# shield.net
KiCad netlist of a schematic drawn in EAGLE
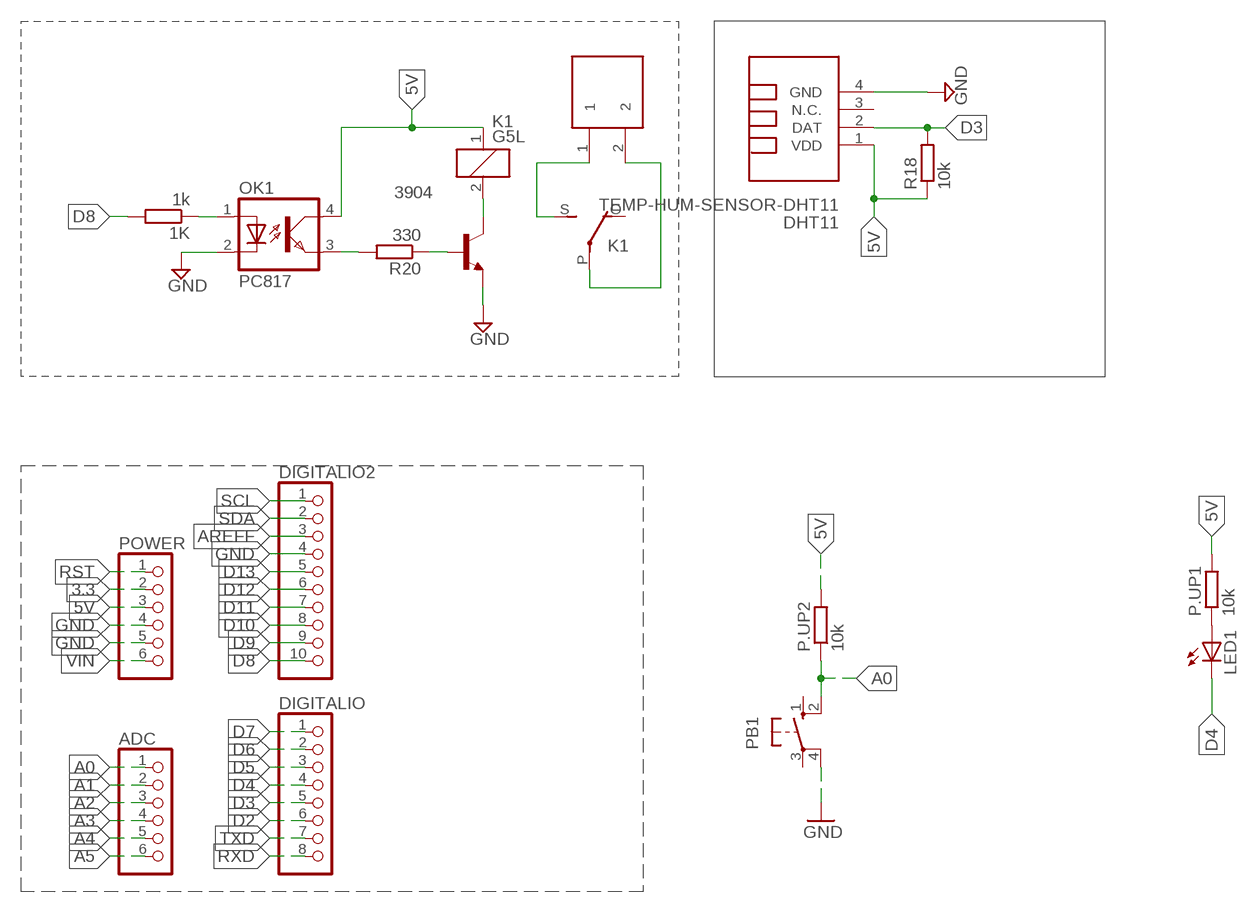
[diagram p0: schematic, sheet 1]

(export (version "E")
  (design (tool "Eeschema 10.0.6"))
  (components
    (comp (ref "1K")
      (value "1k")
      (footprint "eagle-import:R0805")
      (libsource (lib "eagle-import") (part "R-EU_R0805"))
    )
    (comp (ref "3904")
      (value "MMBT3904LT1-NPN-SOT23-BEC")
      (footprint "eagle-import:SOT23-BEC")
      (libsource (lib "eagle-import") (part "-NPN-SOT23-BECMMBT3904LT1"))
    )
    (comp (ref "ADC")
      (value "PINHD-1X6")
      (footprint "eagle-import:1X06")
      (libsource (lib "eagle-import") (part "PINHD-1X6"))
    )
    (comp (ref "DHT11")
      (value "TEMP-HUM-SENSOR-DHT11")
      (footprint "eagle-import:TEMP-HUM-SENSOR-DHT11")
      (libsource (lib "eagle-import") (part "TEMP-HUM-SENSOR-DHT11"))
    )
    (comp (ref "DIGITALIO")
      (value "PINHD-1X8")
      (footprint "eagle-import:1X08")
      (libsource (lib "eagle-import") (part "PINHD-1X8"))
    )
    (comp (ref "DIGITALIO2")
      (value "PINHD-1X10")
      (footprint "eagle-import:1X10")
      (libsource (lib "eagle-import") (part "PINHD-1X10"))
    )
    (comp (ref "K1")
      (value "G5L")
      (footprint "eagle-import:G5LE")
      (libsource (lib "eagle-import") (part "G5L"))
    )
    (comp (ref "LED1")
      (value "LED5MM")
      (footprint "eagle-import:LED5MM")
      (libsource (lib "eagle-import") (part "LED5MM"))
    )
    (comp (ref "OK1")
      (value "PC817")
      (footprint "eagle-import:DIL04")
      (fields (field (name "MPN") "PC817X4J000F"))
      (libsource (lib "eagle-import") (part "PC817"))
    )
    (comp (ref "P.UP1")
      (value "10k")
      (footprint "eagle-import:R0805")
      (libsource (lib "eagle-import") (part "resistor_R-EU_R0805"))
    )
    (comp (ref "P.UP2")
      (value "10k")
      (footprint "eagle-import:R0805")
      (libsource (lib "eagle-import") (part "resistor_R-EU_R0805"))
    )
    (comp (ref "PB1")
      (value "10-XX")
      (footprint "eagle-import:B3F-10XX")
      (fields (field (name "MPN") "B3F-1000"))
      (libsource (lib "eagle-import") (part "10-XX"))
    )
    (comp (ref "POWER")
      (value "PINHD-1X6")
      (footprint "eagle-import:1X06")
      (libsource (lib "eagle-import") (part "PINHD-1X6"))
    )
    (comp (ref "R18")
      (value "10k")
      (footprint "eagle-import:R0805")
      (libsource (lib "eagle-import") (part "R-EU_R0805"))
    )
    (comp (ref "R20")
      (value "330")
      (footprint "eagle-import:R0805")
      (libsource (lib "eagle-import") (part "R-EU_R0805"))
    )
    (comp (ref "U$8")
      (value "TBLOCK2PIN")
      (footprint "eagle-import:2PIN")
      (libsource (lib "eagle-import") (part "TBLOCK2PIN"))
    )
  )
  (nets
    (net (code "1") (name "3.3") (class "Default")
      (node (ref "POWER") (pin "2") (pinfunction "2_2") (pintype "passive"))
    )
    (net (code "2") (name "5V") (class "Default")
      (node (ref "DHT11") (pin "1") (pinfunction "VDD_1") (pintype "power_in"))
      (node (ref "K1") (pin "1") (pinfunction "1_1") (pintype "passive"))
      (node (ref "OK1") (pin "4") (pinfunction "COL_4") (pintype "passive"))
      (node (ref "P.UP1") (pin "2") (pinfunction "2_2") (pintype "passive"))
      (node (ref "P.UP2") (pin "2") (pinfunction "2_2") (pintype "passive"))
      (node (ref "POWER") (pin "3") (pinfunction "3_3") (pintype "passive"))
      (node (ref "R18") (pin "1") (pinfunction "1_1") (pintype "passive"))
    )
    (net (code "3") (name "A0") (class "Default")
      (node (ref "ADC") (pin "1") (pinfunction "1_1") (pintype "passive"))
      (node (ref "P.UP2") (pin "1") (pinfunction "1_1") (pintype "passive"))
      (node (ref "PB1") (pin "2") (pinfunction "S1_2") (pintype "passive"))
    )
    (net (code "4") (name "A1") (class "Default")
      (node (ref "ADC") (pin "2") (pinfunction "2_2") (pintype "passive"))
    )
    (net (code "5") (name "A2") (class "Default")
      (node (ref "ADC") (pin "3") (pinfunction "3_3") (pintype "passive"))
    )
    (net (code "6") (name "A3") (class "Default")
      (node (ref "ADC") (pin "4") (pinfunction "4_4") (pintype "passive"))
    )
    (net (code "7") (name "A4") (class "Default")
      (node (ref "ADC") (pin "5") (pinfunction "5_5") (pintype "passive"))
    )
    (net (code "8") (name "A5") (class "Default")
      (node (ref "ADC") (pin "6") (pinfunction "6_6") (pintype "passive"))
    )
    (net (code "9") (name "AREFF") (class "Default")
      (node (ref "DIGITALIO2") (pin "3") (pinfunction "3_3") (pintype "passive"))
    )
    (net (code "10") (name "D2") (class "Default")
      (node (ref "DIGITALIO") (pin "6") (pinfunction "6_6") (pintype "passive"))
    )
    (net (code "11") (name "D3") (class "Default")
      (node (ref "DHT11") (pin "2") (pinfunction "DAT_2") (pintype "bidirectional"))
      (node (ref "DIGITALIO") (pin "5") (pinfunction "5_5") (pintype "passive"))
      (node (ref "R18") (pin "2") (pinfunction "2_2") (pintype "passive"))
    )
    (net (code "12") (name "D4") (class "Default")
      (node (ref "DIGITALIO") (pin "4") (pinfunction "4_4") (pintype "passive"))
      (node (ref "LED1") (pin "K") (pinfunction "C_K") (pintype "passive"))
    )
    (net (code "13") (name "D5") (class "Default")
      (node (ref "DIGITALIO") (pin "3") (pinfunction "3_3") (pintype "passive"))
    )
    (net (code "14") (name "D6") (class "Default")
      (node (ref "DIGITALIO") (pin "2") (pinfunction "2_2") (pintype "passive"))
    )
    (net (code "15") (name "D7") (class "Default")
      (node (ref "DIGITALIO") (pin "1") (pinfunction "1_1") (pintype "passive"))
    )
    (net (code "16") (name "D8") (class "Default")
      (node (ref "1K") (pin "2") (pinfunction "2_2") (pintype "passive"))
      (node (ref "DIGITALIO2") (pin "10") (pinfunction "10_10") (pintype "passive"))
    )
    (net (code "17") (name "D9") (class "Default")
      (node (ref "DIGITALIO2") (pin "9") (pinfunction "9_9") (pintype "passive"))
    )
    (net (code "18") (name "D10") (class "Default")
      (node (ref "DIGITALIO2") (pin "8") (pinfunction "8_8") (pintype "passive"))
    )
    (net (code "19") (name "D11") (class "Default")
      (node (ref "DIGITALIO2") (pin "7") (pinfunction "7_7") (pintype "passive"))
    )
    (net (code "20") (name "D12") (class "Default")
      (node (ref "DIGITALIO2") (pin "6") (pinfunction "6_6") (pintype "passive"))
    )
    (net (code "21") (name "D13") (class "Default")
      (node (ref "DIGITALIO2") (pin "5") (pinfunction "5_5") (pintype "passive"))
    )
    (net (code "22") (name "GND") (class "Default")
      (node (ref "3904") (pin "E") (pinfunction "E_E") (pintype "passive"))
      (node (ref "DHT11") (pin "4") (pinfunction "GND_4") (pintype "power_in"))
      (node (ref "DIGITALIO2") (pin "4") (pinfunction "4_4") (pintype "passive"))
      (node (ref "OK1") (pin "2") (pinfunction "C_2") (pintype "passive"))
      (node (ref "PB1") (pin "4") (pinfunction "P1_4") (pintype "passive"))
      (node (ref "POWER") (pin "4") (pinfunction "4_4") (pintype "passive"))
      (node (ref "POWER") (pin "5") (pinfunction "5_5") (pintype "passive"))
    )
    (net (code "23") (name "Net-(3904-PadB)") (class "Default")
      (node (ref "3904") (pin "B") (pinfunction "B_B") (pintype "passive"))
      (node (ref "R20") (pin "1") (pinfunction "1_1") (pintype "passive"))
    )
    (net (code "24") (name "Net-(3904-PadC)") (class "Default")
      (node (ref "3904") (pin "C") (pinfunction "C_C") (pintype "passive"))
      (node (ref "K1") (pin "2") (pinfunction "2_2") (pintype "passive"))
    )
    (net (code "25") (name "Net-(K1-PadP)") (class "Default")
      (node (ref "K1") (pin "P") (pinfunction "P_P") (pintype "passive"))
      (node (ref "U$8") (pin "2") (pinfunction "2_2") (pintype "bidirectional"))
    )
    (net (code "26") (name "Net-(K1-PadS)") (class "Default")
      (node (ref "K1") (pin "S") (pinfunction "S_S") (pintype "passive"))
      (node (ref "U$8") (pin "1") (pinfunction "1_1") (pintype "bidirectional"))
    )
    (net (code "27") (name "Net-(LED1-PadA)") (class "Default")
      (node (ref "LED1") (pin "A") (pinfunction "A_A") (pintype "passive"))
      (node (ref "P.UP1") (pin "1") (pinfunction "1_1") (pintype "passive"))
    )
    (net (code "28") (name "Net-(OK1-A)") (class "Default")
      (node (ref "1K") (pin "1") (pinfunction "1_1") (pintype "passive"))
      (node (ref "OK1") (pin "1") (pinfunction "A_1") (pintype "passive"))
    )
    (net (code "29") (name "Net-(OK1-EMIT)") (class "Default")
      (node (ref "OK1") (pin "3") (pinfunction "EMIT_3") (pintype "passive"))
      (node (ref "R20") (pin "2") (pinfunction "2_2") (pintype "passive"))
    )
    (net (code "30") (name "RST") (class "Default")
      (node (ref "POWER") (pin "1") (pinfunction "1_1") (pintype "passive"))
    )
    (net (code "31") (name "RXD") (class "Default")
      (node (ref "DIGITALIO") (pin "8") (pinfunction "8_8") (pintype "passive"))
    )
    (net (code "32") (name "SCL") (class "Default")
      (node (ref "DIGITALIO2") (pin "1") (pinfunction "1_1") (pintype "passive"))
    )
    (net (code "33") (name "SDA") (class "Default")
      (node (ref "DIGITALIO2") (pin "2") (pinfunction "2_2") (pintype "passive"))
    )
    (net (code "34") (name "TXD") (class "Default")
      (node (ref "DIGITALIO") (pin "7") (pinfunction "7_7") (pintype "passive"))
    )
    (net (code "35") (name "VIN") (class "Default")
      (node (ref "POWER") (pin "6") (pinfunction "6_6") (pintype "passive"))
    )
    (net (code "36") (name "unconnected-(DHT11-N.C.-Pad3)") (class "Default")
      (node (ref "DHT11") (pin "3") (pinfunction "N.C._3") (pintype "passive"))
    )
    (net (code "37") (name "unconnected-(K1-PadO)") (class "Default")
      (node (ref "K1") (pin "O") (pinfunction "O_O") (pintype "passive"))
    )
    (net (code "38") (name "unconnected-(PB1-P-Pad3)") (class "Default")
      (node (ref "PB1") (pin "3") (pinfunction "P_3") (pintype "passive"))
    )
    (net (code "39") (name "unconnected-(PB1-S-Pad1)") (class "Default")
      (node (ref "PB1") (pin "1") (pinfunction "S_1") (pintype "passive"))
    )
  )
)
